# USB3_Controller_Schematics.net
KiCad netlist of a schematic drawn in Altium Designer
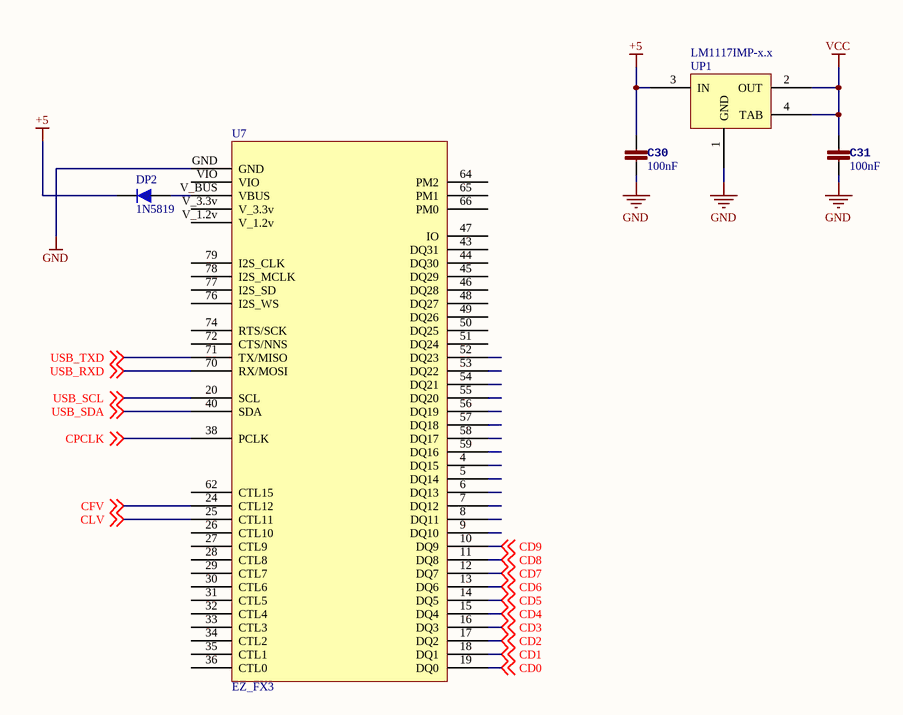
[diagram p0: USB3_Controller_Schematics.SchDoc]

(export (version "E")
  (design (tool "Eeschema 10.0.6"))
  (components
    (comp (ref "C30")
      (value "100nF")
      (footprint "_0805")
      (fields (field (name "Comment") "Cap"))
      (libsource (lib "Passives_Integrated_Library") (part "Cap_1"))
    )
    (comp (ref "C31")
      (value "100nF")
      (footprint "_0805")
      (fields (field (name "Comment") "Cap"))
      (libsource (lib "Passives_Integrated_Library") (part "Cap_1"))
    )
    (comp (ref "DP2")
      (value "1N5819")
      (footprint "430X270D")
      (description "Schottkey Rectifiers")
      (fields (field (name "DESIGNER") "Abbas Basereh"))
      (libsource (lib "Diodes_Integrated_Library") (part "1N5819"))
    )
    (comp (ref "U7")
      (value "EZ_FX3")
      (footprint "EZ_FX3")
      (libsource (lib "Boards_ans_moduls_Integrated_Library") (part "EZ_FX3"))
    )
    (comp (ref "UP1")
      (value "LM1117IMP-x.x")
      (footprint "SOT223_4")
      (description "x.x Volt, 800mA Low-Dropout Linear Regulator, 4-pin SOT-223")
      (fields (field (name "DESIGNER") "Abbas Basereh"))
      (libsource (lib "Regulators_Integrated_Library") (part "LM1117IMP-x.x"))
    )
  )
  (nets
    (net (code "1") (name "+5") (class "Default")
      (node (ref "C30") (pin "1") (pinfunction "1_1") (pintype "passive"))
      (node (ref "DP2") (pin "2") (pintype "passive"))
      (node (ref "UP1") (pin "3") (pinfunction "IN_3") (pintype "power_in"))
    )
    (net (code "2") (name "CD0") (class "Default")
      (node (ref "U7") (pin "19") (pinfunction "DQ0_19") (pintype "passive"))
    )
    (net (code "3") (name "CD1") (class "Default")
      (node (ref "U7") (pin "18") (pinfunction "DQ1_18") (pintype "passive"))
    )
    (net (code "4") (name "CD2") (class "Default")
      (node (ref "U7") (pin "17") (pinfunction "DQ2_17") (pintype "passive"))
    )
    (net (code "5") (name "CD3") (class "Default")
      (node (ref "U7") (pin "16") (pinfunction "DQ3_16") (pintype "passive"))
    )
    (net (code "6") (name "CD4") (class "Default")
      (node (ref "U7") (pin "15") (pinfunction "DQ4_15") (pintype "passive"))
    )
    (net (code "7") (name "CD5") (class "Default")
      (node (ref "U7") (pin "14") (pinfunction "DQ5_14") (pintype "passive"))
    )
    (net (code "8") (name "CD6") (class "Default")
      (node (ref "U7") (pin "13") (pinfunction "DQ6_13") (pintype "passive"))
    )
    (net (code "9") (name "CD7") (class "Default")
      (node (ref "U7") (pin "12") (pinfunction "DQ7_12") (pintype "passive"))
    )
    (net (code "10") (name "CD8") (class "Default")
      (node (ref "U7") (pin "11") (pinfunction "DQ8_11") (pintype "passive"))
    )
    (net (code "11") (name "CD9") (class "Default")
      (node (ref "U7") (pin "10") (pinfunction "DQ9_10") (pintype "passive"))
    )
    (net (code "12") (name "CFV") (class "Default")
      (node (ref "U7") (pin "24") (pinfunction "CTL12_24") (pintype "passive"))
    )
    (net (code "13") (name "CLV") (class "Default")
      (node (ref "U7") (pin "25") (pinfunction "CTL11_25") (pintype "passive"))
    )
    (net (code "14") (name "CPCLK") (class "Default")
      (node (ref "U7") (pin "38") (pinfunction "PCLK_38") (pintype "passive"))
    )
    (net (code "15") (name "GND") (class "Default")
      (node (ref "C30") (pin "2") (pinfunction "2_2") (pintype "passive"))
      (node (ref "C31") (pin "2") (pinfunction "2_2") (pintype "passive"))
      (node (ref "U7") (pin "GND") (pinfunction "GND_GND") (pintype "passive"))
      (node (ref "UP1") (pin "1") (pinfunction "GND_1") (pintype "power_in"))
    )
    (net (code "16") (name "Net-(U7-VBUS)") (class "Default")
      (node (ref "DP2") (pin "1") (pintype "passive"))
      (node (ref "U7") (pin "V_BUS") (pinfunction "VBUS_V_BUS") (pintype "passive"))
    )
    (net (code "17") (name "USB_RXD") (class "Default")
      (node (ref "U7") (pin "70") (pinfunction "RX/MOSI_70") (pintype "passive"))
    )
    (net (code "18") (name "USB_SCL") (class "Default")
      (node (ref "U7") (pin "20") (pinfunction "SCL_20") (pintype "passive"))
    )
    (net (code "19") (name "USB_SDA") (class "Default")
      (node (ref "U7") (pin "40") (pinfunction "SDA_40") (pintype "passive"))
    )
    (net (code "20") (name "USB_TXD") (class "Default")
      (node (ref "U7") (pin "71") (pinfunction "TX/MISO_71") (pintype "passive"))
    )
    (net (code "21") (name "VCC") (class "Default")
      (node (ref "C31") (pin "1") (pinfunction "1_1") (pintype "passive"))
      (node (ref "UP1") (pin "2") (pinfunction "OUT_2") (pintype "power_in"))
      (node (ref "UP1") (pin "4") (pinfunction "TAB_4") (pintype "power_in"))
    )
    (net (code "22") (name "unconnected-(U7-CTL0-Pad36)") (class "Default")
      (node (ref "U7") (pin "36") (pinfunction "CTL0_36") (pintype "passive"))
    )
    (net (code "23") (name "unconnected-(U7-CTL1-Pad35)") (class "Default")
      (node (ref "U7") (pin "35") (pinfunction "CTL1_35") (pintype "passive"))
    )
    (net (code "24") (name "unconnected-(U7-CTL2-Pad34)") (class "Default")
      (node (ref "U7") (pin "34") (pinfunction "CTL2_34") (pintype "passive"))
    )
    (net (code "25") (name "unconnected-(U7-CTL3-Pad33)") (class "Default")
      (node (ref "U7") (pin "33") (pinfunction "CTL3_33") (pintype "passive"))
    )
    (net (code "26") (name "unconnected-(U7-CTL4-Pad32)") (class "Default")
      (node (ref "U7") (pin "32") (pinfunction "CTL4_32") (pintype "passive"))
    )
    (net (code "27") (name "unconnected-(U7-CTL5-Pad31)") (class "Default")
      (node (ref "U7") (pin "31") (pinfunction "CTL5_31") (pintype "passive"))
    )
    (net (code "28") (name "unconnected-(U7-CTL6-Pad30)") (class "Default")
      (node (ref "U7") (pin "30") (pinfunction "CTL6_30") (pintype "passive"))
    )
    (net (code "29") (name "unconnected-(U7-CTL7-Pad29)") (class "Default")
      (node (ref "U7") (pin "29") (pinfunction "CTL7_29") (pintype "passive"))
    )
    (net (code "30") (name "unconnected-(U7-CTL8-Pad28)") (class "Default")
      (node (ref "U7") (pin "28") (pinfunction "CTL8_28") (pintype "passive"))
    )
    (net (code "31") (name "unconnected-(U7-CTL9-Pad27)") (class "Default")
      (node (ref "U7") (pin "27") (pinfunction "CTL9_27") (pintype "passive"))
    )
    (net (code "32") (name "unconnected-(U7-CTL10-Pad26)") (class "Default")
      (node (ref "U7") (pin "26") (pinfunction "CTL10_26") (pintype "passive"))
    )
    (net (code "33") (name "unconnected-(U7-CTL15-Pad62)") (class "Default")
      (node (ref "U7") (pin "62") (pinfunction "CTL15_62") (pintype "passive"))
    )
    (net (code "34") (name "unconnected-(U7-CTS{slash}NNS-Pad72)") (class "Default")
      (node (ref "U7") (pin "72") (pinfunction "CTS/NNS_72") (pintype "passive"))
    )
    (net (code "35") (name "unconnected-(U7-DQ10-Pad9)") (class "Default")
      (node (ref "U7") (pin "9") (pinfunction "DQ10_9") (pintype "passive"))
    )
    (net (code "36") (name "unconnected-(U7-DQ11-Pad8)") (class "Default")
      (node (ref "U7") (pin "8") (pinfunction "DQ11_8") (pintype "passive"))
    )
    (net (code "37") (name "unconnected-(U7-DQ12-Pad7)") (class "Default")
      (node (ref "U7") (pin "7") (pinfunction "DQ12_7") (pintype "passive"))
    )
    (net (code "38") (name "unconnected-(U7-DQ13-Pad6)") (class "Default")
      (node (ref "U7") (pin "6") (pinfunction "DQ13_6") (pintype "passive"))
    )
    (net (code "39") (name "unconnected-(U7-DQ14-Pad5)") (class "Default")
      (node (ref "U7") (pin "5") (pinfunction "DQ14_5") (pintype "passive"))
    )
    (net (code "40") (name "unconnected-(U7-DQ15-Pad4)") (class "Default")
      (node (ref "U7") (pin "4") (pinfunction "DQ15_4") (pintype "passive"))
    )
    (net (code "41") (name "unconnected-(U7-DQ16-Pad59)") (class "Default")
      (node (ref "U7") (pin "59") (pinfunction "DQ16_59") (pintype "passive"))
    )
    (net (code "42") (name "unconnected-(U7-DQ17-Pad58)") (class "Default")
      (node (ref "U7") (pin "58") (pinfunction "DQ17_58") (pintype "passive"))
    )
    (net (code "43") (name "unconnected-(U7-DQ18-Pad57)") (class "Default")
      (node (ref "U7") (pin "57") (pinfunction "DQ18_57") (pintype "passive"))
    )
    (net (code "44") (name "unconnected-(U7-DQ19-Pad56)") (class "Default")
      (node (ref "U7") (pin "56") (pinfunction "DQ19_56") (pintype "passive"))
    )
    (net (code "45") (name "unconnected-(U7-DQ20-Pad55)") (class "Default")
      (node (ref "U7") (pin "55") (pinfunction "DQ20_55") (pintype "passive"))
    )
    (net (code "46") (name "unconnected-(U7-DQ21-Pad54)") (class "Default")
      (node (ref "U7") (pin "54") (pinfunction "DQ21_54") (pintype "passive"))
    )
    (net (code "47") (name "unconnected-(U7-DQ22-Pad53)") (class "Default")
      (node (ref "U7") (pin "53") (pinfunction "DQ22_53") (pintype "passive"))
    )
    (net (code "48") (name "unconnected-(U7-DQ23-Pad52)") (class "Default")
      (node (ref "U7") (pin "52") (pinfunction "DQ23_52") (pintype "passive"))
    )
    (net (code "49") (name "unconnected-(U7-DQ24-Pad51)") (class "Default")
      (node (ref "U7") (pin "51") (pinfunction "DQ24_51") (pintype "passive"))
    )
    (net (code "50") (name "unconnected-(U7-DQ25-Pad50)") (class "Default")
      (node (ref "U7") (pin "50") (pinfunction "DQ25_50") (pintype "passive"))
    )
    (net (code "51") (name "unconnected-(U7-DQ26-Pad49)") (class "Default")
      (node (ref "U7") (pin "49") (pinfunction "DQ26_49") (pintype "passive"))
    )
    (net (code "52") (name "unconnected-(U7-DQ27-Pad48)") (class "Default")
      (node (ref "U7") (pin "48") (pinfunction "DQ27_48") (pintype "passive"))
    )
    (net (code "53") (name "unconnected-(U7-DQ28-Pad46)") (class "Default")
      (node (ref "U7") (pin "46") (pinfunction "DQ28_46") (pintype "passive"))
    )
    (net (code "54") (name "unconnected-(U7-DQ29-Pad45)") (class "Default")
      (node (ref "U7") (pin "45") (pinfunction "DQ29_45") (pintype "passive"))
    )
    (net (code "55") (name "unconnected-(U7-DQ30-Pad44)") (class "Default")
      (node (ref "U7") (pin "44") (pinfunction "DQ30_44") (pintype "passive"))
    )
    (net (code "56") (name "unconnected-(U7-DQ31-Pad43)") (class "Default")
      (node (ref "U7") (pin "43") (pinfunction "DQ31_43") (pintype "passive"))
    )
    (net (code "57") (name "unconnected-(U7-I2S_CLK-Pad79)") (class "Default")
      (node (ref "U7") (pin "79") (pinfunction "I2S_CLK_79") (pintype "passive"))
    )
    (net (code "58") (name "unconnected-(U7-I2S_MCLK-Pad78)") (class "Default")
      (node (ref "U7") (pin "78") (pinfunction "I2S_MCLK_78") (pintype "passive"))
    )
    (net (code "59") (name "unconnected-(U7-I2S_SD-Pad77)") (class "Default")
      (node (ref "U7") (pin "77") (pinfunction "I2S_SD_77") (pintype "passive"))
    )
    (net (code "60") (name "unconnected-(U7-I2S_WS-Pad76)") (class "Default")
      (node (ref "U7") (pin "76") (pinfunction "I2S_WS_76") (pintype "passive"))
    )
    (net (code "61") (name "unconnected-(U7-IO-Pad47)") (class "Default")
      (node (ref "U7") (pin "47") (pinfunction "IO_47") (pintype "passive"))
    )
    (net (code "62") (name "unconnected-(U7-PM0-Pad66)") (class "Default")
      (node (ref "U7") (pin "66") (pinfunction "PM0_66") (pintype "passive"))
    )
    (net (code "63") (name "unconnected-(U7-PM1-Pad65)") (class "Default")
      (node (ref "U7") (pin "65") (pinfunction "PM1_65") (pintype "passive"))
    )
    (net (code "64") (name "unconnected-(U7-PM2-Pad64)") (class "Default")
      (node (ref "U7") (pin "64") (pinfunction "PM2_64") (pintype "passive"))
    )
    (net (code "65") (name "unconnected-(U7-PadVIO)") (class "Default")
      (node (ref "U7") (pin "VIO") (pinfunction "VIO_VIO") (pintype "passive"))
    )
    (net (code "66") (name "unconnected-(U7-PadV_1.2v)") (class "Default")
      (node (ref "U7") (pin "V_1.2v") (pinfunction "V_1.2v_V_1.2v") (pintype "passive"))
    )
    (net (code "67") (name "unconnected-(U7-PadV_3.3v)") (class "Default")
      (node (ref "U7") (pin "V_3.3v") (pinfunction "V_3.3v_V_3.3v") (pintype "passive"))
    )
    (net (code "68") (name "unconnected-(U7-RTS{slash}SCK-Pad74)") (class "Default")
      (node (ref "U7") (pin "74") (pinfunction "RTS/SCK_74") (pintype "passive"))
    )
  )
)
